# TPS54540_V2.net
KiCad netlist of a schematic drawn in Altium Designer
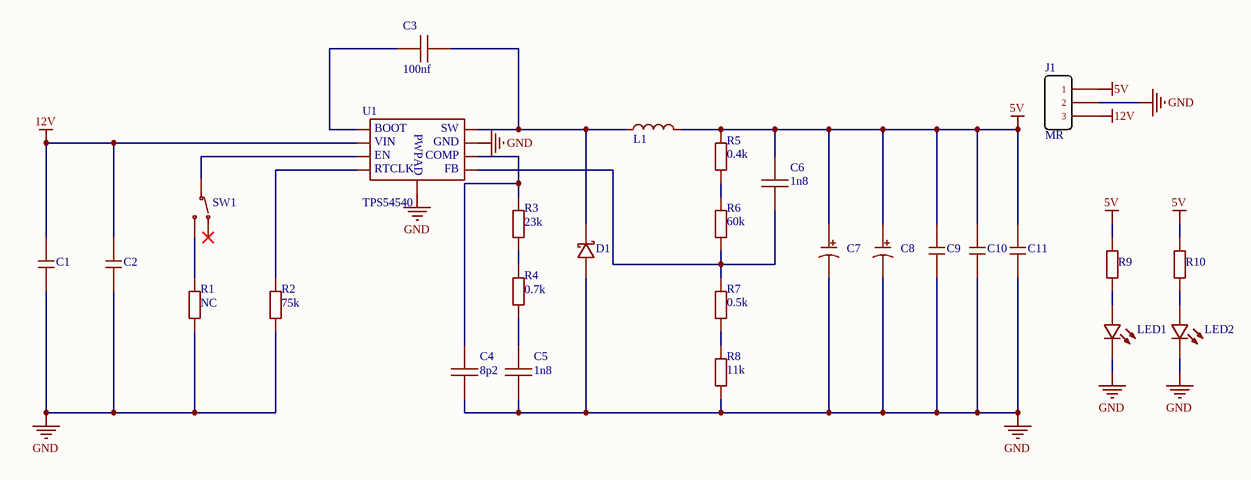
[diagram p0: TPS54540_V2.SchDoc]

(export (version "E")
  (design (tool "Eeschema 10.0.6"))
  (components
    (comp (ref "C1") (value "4u7") (footprint "0805C") (libsource (lib "元件库") (part "电容_贴片")))
    (comp (ref "C2") (value "4u7") (footprint "0805C") (libsource (lib "元件库") (part "电容_贴片")))
    (comp (ref "C3") (value "100nf") (footprint "0603C") (libsource (lib "") (part "电容_贴片_1")))
    (comp (ref "C4") (value "8p2") (footprint "0603C") (libsource (lib "") (part "电容_贴片_1")))
    (comp (ref "C5") (value "1n8") (footprint "0603C") (libsource (lib "") (part "电容_贴片_1")))
    (comp (ref "C6") (value "1n8") (footprint "0603C") (libsource (lib "") (part "电容_贴片_1")))
    (comp (ref "C7") (value "47uF") (footprint "SVP6.3") (libsource (lib "元件库") (part "电容_贴片电解")))
    (comp (ref "C8") (value "47uF") (footprint "3528B/1210") (libsource (lib "元件库") (part "电容_贴片钽")))
    (comp (ref "C9") (value "22uF") (footprint "0805C") (libsource (lib "元件库") (part "电容_贴片")))
    (comp (ref "C10") (value "22uF") (footprint "0805C") (libsource (lib "元件库") (part "电容_贴片")))
    (comp (ref "C11") (value "NC") (footprint "0805C") (libsource (lib "元件库") (part "电容_贴片")))
    (comp (ref "D1") (value "1054") (footprint "TO-277") (libsource (lib "元件库") (part "二极管_肖特基")))
    (comp (ref "J1") (value "MR") (footprint "MR30-FB") (libsource (lib "接口库") (part "接口_MR")))
    (comp (ref "L1") (value "2u2") (footprint "10XXL") (libsource (lib "元件库") (part "电感_贴片")))
    (comp (ref "LED1") (value "LED") (footprint "0603D") (libsource (lib "元件库") (part "二极管_贴片发光")))
    (comp (ref "LED2") (value "LED") (footprint "0603D") (libsource (lib "元件库") (part "二极管_贴片发光")))
    (comp (ref "R1") (value "NC") (footprint "0603R") (libsource (lib "元件库") (part "电阻_贴片")))
    (comp (ref "R2") (value "75k") (footprint "0603R") (libsource (lib "元件库") (part "电阻_贴片")))
    (comp (ref "R3") (value "23k") (footprint "0603R") (libsource (lib "元件库") (part "电阻_贴片")))
    (comp (ref "R4") (value "0.7k") (footprint "0603R") (libsource (lib "元件库") (part "电阻_贴片")))
    (comp (ref "R5") (value "0.4k") (footprint "0603R") (libsource (lib "元件库") (part "电阻_贴片")))
    (comp (ref "R6") (value "60k") (footprint "0603R") (libsource (lib "元件库") (part "电阻_贴片")))
    (comp (ref "R7") (value "0.5k") (footprint "0603R") (libsource (lib "元件库") (part "电阻_贴片")))
    (comp (ref "R8") (value "11k") (footprint "0603R") (libsource (lib "元件库") (part "电阻_贴片")))
    (comp (ref "R9") (value "4K7") (footprint "0603R") (libsource (lib "") (part "电阻_贴片_1")))
    (comp (ref "R10") (value "4K7") (footprint "0603R") (libsource (lib "") (part "电阻_贴片_1")))
    (comp (ref "SW1") (value "开关") (footprint "*SW-1280S") (libsource (lib "元件库") (part "开关_三脚")))
    (comp (ref "U1")
      (value "TPS54540")
      (footprint "SOP-8-PP")
      (libsource (lib "元件库") (part "芯片/IC-TPS54540"))
    )
  )
  (nets
    (net (code "1") (name "5V") (class "Default")
      (node (ref "C10") (pin "1") (pinfunction "1_1") (pintype "passive"))
      (node (ref "C11") (pin "1") (pinfunction "1_1") (pintype "passive"))
      (node (ref "C6") (pin "2") (pinfunction "2_2") (pintype "passive"))
      (node (ref "C7") (pin "1") (pinfunction "1_1") (pintype "passive"))
      (node (ref "C8") (pin "1") (pinfunction "1_1") (pintype "passive"))
      (node (ref "C9") (pin "1") (pinfunction "1_1") (pintype "passive"))
      (node (ref "J1") (pin "1") (pinfunction "1_1") (pintype "passive"))
      (node (ref "L1") (pin "2") (pinfunction "2_2") (pintype "passive"))
      (node (ref "R10") (pin "1") (pinfunction "1_1") (pintype "passive"))
      (node (ref "R5") (pin "2") (pinfunction "2_2") (pintype "passive"))
      (node (ref "R9") (pin "1") (pinfunction "1_1") (pintype "passive"))
    )
    (net (code "2") (name "12V") (class "Default")
      (node (ref "C1") (pin "2") (pinfunction "2_2") (pintype "passive"))
      (node (ref "C2") (pin "2") (pinfunction "2_2") (pintype "passive"))
      (node (ref "J1") (pin "3") (pinfunction "3_3") (pintype "passive"))
      (node (ref "U1") (pin "2") (pinfunction "2_2") (pintype "passive"))
    )
    (net (code "3") (name "GND") (class "Default")
      (node (ref "C1") (pin "1") (pinfunction "1_1") (pintype "passive"))
      (node (ref "C10") (pin "2") (pinfunction "2_2") (pintype "passive"))
      (node (ref "C11") (pin "2") (pinfunction "2_2") (pintype "passive"))
      (node (ref "C2") (pin "1") (pinfunction "1_1") (pintype "passive"))
      (node (ref "C4") (pin "2") (pinfunction "2_2") (pintype "passive"))
      (node (ref "C5") (pin "2") (pinfunction "2_2") (pintype "passive"))
      (node (ref "C7") (pin "2") (pinfunction "2_2") (pintype "passive"))
      (node (ref "C8") (pin "2") (pinfunction "2_2") (pintype "passive"))
      (node (ref "C9") (pin "2") (pinfunction "2_2") (pintype "passive"))
      (node (ref "D1") (pin "1") (pinfunction "1_1") (pintype "passive"))
      (node (ref "J1") (pin "2") (pinfunction "2_2") (pintype "passive"))
      (node (ref "LED1") (pin "2") (pinfunction "2_2") (pintype "passive"))
      (node (ref "LED2") (pin "2") (pinfunction "2_2") (pintype "passive"))
      (node (ref "R1") (pin "1") (pinfunction "1_1") (pintype "passive"))
      (node (ref "R2") (pin "1") (pinfunction "1_1") (pintype "passive"))
      (node (ref "R8") (pin "1") (pinfunction "1_1") (pintype "passive"))
      (node (ref "U1") (pin "7") (pinfunction "7_7") (pintype "passive"))
      (node (ref "U1") (pin "9") (pinfunction "9_9") (pintype "passive"))
    )
    (net (code "4") (name "Net-(C3-Pad1)") (class "Default")
      (node (ref "C3") (pin "1") (pinfunction "1_1") (pintype "passive"))
      (node (ref "U1") (pin "1") (pinfunction "1_1") (pintype "passive"))
    )
    (net (code "5") (name "Net-(C3-Pad2)") (class "Default")
      (node (ref "C3") (pin "2") (pinfunction "2_2") (pintype "passive"))
      (node (ref "D1") (pin "2") (pinfunction "2_2") (pintype "passive"))
      (node (ref "L1") (pin "1") (pinfunction "1_1") (pintype "passive"))
      (node (ref "U1") (pin "8") (pinfunction "8_8") (pintype "passive"))
    )
    (net (code "6") (name "Net-(C4-Pad1)") (class "Default")
      (node (ref "C4") (pin "1") (pinfunction "1_1") (pintype "passive"))
      (node (ref "R3") (pin "2") (pinfunction "2_2") (pintype "passive"))
      (node (ref "U1") (pin "6") (pinfunction "6_6") (pintype "passive"))
    )
    (net (code "7") (name "Net-(C5-Pad1)") (class "Default")
      (node (ref "C5") (pin "1") (pinfunction "1_1") (pintype "passive"))
      (node (ref "R4") (pin "1") (pinfunction "1_1") (pintype "passive"))
    )
    (net (code "8") (name "Net-(C6-Pad1)") (class "Default")
      (node (ref "C6") (pin "1") (pinfunction "1_1") (pintype "passive"))
      (node (ref "R6") (pin "1") (pinfunction "1_1") (pintype "passive"))
      (node (ref "R7") (pin "2") (pinfunction "2_2") (pintype "passive"))
      (node (ref "U1") (pin "5") (pinfunction "5_5") (pintype "passive"))
    )
    (net (code "9") (name "Net-(LED1-Pad1)") (class "Default")
      (node (ref "LED1") (pin "1") (pinfunction "1_1") (pintype "passive"))
      (node (ref "R9") (pin "2") (pinfunction "2_2") (pintype "passive"))
    )
    (net (code "10") (name "Net-(LED2-Pad1)") (class "Default")
      (node (ref "LED2") (pin "1") (pinfunction "1_1") (pintype "passive"))
      (node (ref "R10") (pin "2") (pinfunction "2_2") (pintype "passive"))
    )
    (net (code "11") (name "Net-(R1-Pad2)") (class "Default")
      (node (ref "R1") (pin "2") (pinfunction "2_2") (pintype "passive"))
      (node (ref "SW1") (pin "3") (pinfunction "3_3") (pintype "passive"))
    )
    (net (code "12") (name "Net-(R2-Pad2)") (class "Default")
      (node (ref "R2") (pin "2") (pinfunction "2_2") (pintype "passive"))
      (node (ref "U1") (pin "4") (pinfunction "4_4") (pintype "passive"))
    )
    (net (code "13") (name "Net-(R3-Pad1)") (class "Default")
      (node (ref "R3") (pin "1") (pinfunction "1_1") (pintype "passive"))
      (node (ref "R4") (pin "2") (pinfunction "2_2") (pintype "passive"))
    )
    (net (code "14") (name "Net-(R5-Pad1)") (class "Default")
      (node (ref "R5") (pin "1") (pinfunction "1_1") (pintype "passive"))
      (node (ref "R6") (pin "2") (pinfunction "2_2") (pintype "passive"))
    )
    (net (code "15") (name "Net-(R7-Pad1)") (class "Default")
      (node (ref "R7") (pin "1") (pinfunction "1_1") (pintype "passive"))
      (node (ref "R8") (pin "2") (pinfunction "2_2") (pintype "passive"))
    )
    (net (code "16") (name "Net-(SW1-Pad1)") (class "Default")
      (node (ref "SW1") (pin "1") (pinfunction "1_1") (pintype "passive"))
      (node (ref "U1") (pin "3") (pinfunction "3_3") (pintype "passive"))
    )
    (net (code "17") (name "unconnected-(SW1-Pad2)") (class "Default")
      (node (ref "SW1") (pin "2") (pinfunction "2_2") (pintype "passive+no_connect"))
    )
  )
)
